# MotoControl_V1_0.net
KiCad netlist of a schematic drawn in Altium Designer
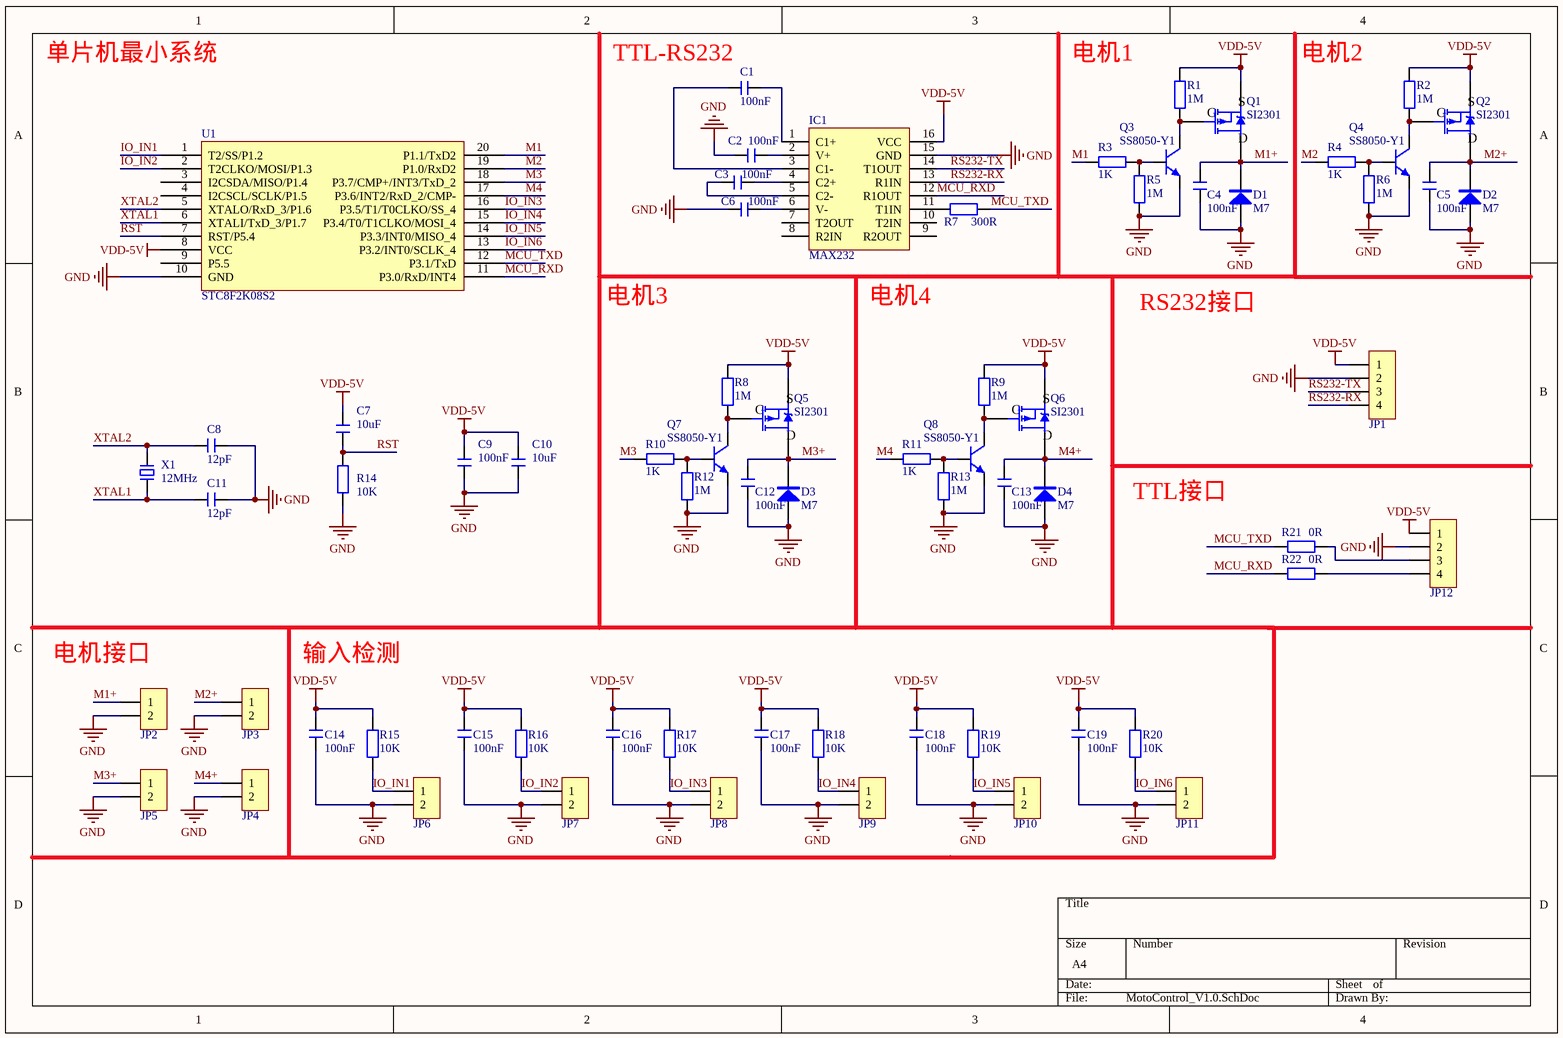
[diagram p0: MotoControl_V1.0.SchDoc]

(export (version "E")
  (design (tool "Eeschema 10.0.6"))
  (components
    (comp (ref "C1")
      (value "100nF")
      (footprint "C_0603")
      (description "无极性贴片电容")
      (fields (field (name "版权") "iSAIGU"))
      (libsource (lib "1-电阻-电容-电感") (part "C"))
    )
    (comp (ref "C2")
      (value "100nF")
      (footprint "C_0603")
      (description "无极性贴片电容")
      (fields (field (name "版权") "iSAIGU"))
      (libsource (lib "1-电阻-电容-电感") (part "C"))
    )
    (comp (ref "C3")
      (value "100nF")
      (footprint "C_0603")
      (description "无极性贴片电容")
      (fields (field (name "版权") "iSAIGU"))
      (libsource (lib "1-电阻-电容-电感") (part "C"))
    )
    (comp (ref "C4")
      (value "100nF")
      (footprint "C_0603")
      (description "无极性贴片电容")
      (fields (field (name "版权") "iSAIGU"))
      (libsource (lib "1-电阻-电容-电感") (part "C"))
    )
    (comp (ref "C5")
      (value "100nF")
      (footprint "C_0603")
      (description "无极性贴片电容")
      (fields (field (name "版权") "iSAIGU"))
      (libsource (lib "1-电阻-电容-电感") (part "C"))
    )
    (comp (ref "C6")
      (value "100nF")
      (footprint "C_0603")
      (description "无极性贴片电容")
      (fields (field (name "版权") "iSAIGU"))
      (libsource (lib "1-电阻-电容-电感") (part "C"))
    )
    (comp (ref "C7")
      (value "10uF")
      (footprint "C_0603")
      (description "无极性贴片电容")
      (fields (field (name "版权") "iSAIGU"))
      (libsource (lib "1-电阻-电容-电感") (part "C"))
    )
    (comp (ref "C8")
      (value "12pF")
      (footprint "C_0603")
      (description "无极性贴片电容")
      (fields (field (name "版权") "iSAIGU"))
      (libsource (lib "1-电阻-电容-电感") (part "C"))
    )
    (comp (ref "C9")
      (value "100nF")
      (footprint "C_0603")
      (description "无极性贴片电容")
      (fields (field (name "版权") "iSAIGU"))
      (libsource (lib "1-电阻-电容-电感") (part "C"))
    )
    (comp (ref "C10")
      (value "10uF")
      (footprint "C_0603")
      (description "无极性贴片电容")
      (fields (field (name "版权") "iSAIGU"))
      (libsource (lib "1-电阻-电容-电感") (part "C"))
    )
    (comp (ref "C11")
      (value "12pF")
      (footprint "C_0603")
      (description "无极性贴片电容")
      (fields (field (name "版权") "iSAIGU"))
      (libsource (lib "1-电阻-电容-电感") (part "C"))
    )
    (comp (ref "C12")
      (value "100nF")
      (footprint "C_0603")
      (description "无极性贴片电容")
      (fields (field (name "版权") "iSAIGU"))
      (libsource (lib "1-电阻-电容-电感") (part "C"))
    )
    (comp (ref "C13")
      (value "100nF")
      (footprint "C_0603")
      (description "无极性贴片电容")
      (fields (field (name "版权") "iSAIGU"))
      (libsource (lib "1-电阻-电容-电感") (part "C"))
    )
    (comp (ref "C14")
      (value "100nF")
      (footprint "C_0603")
      (description "无极性贴片电容")
      (fields (field (name "版权") "iSAIGU"))
      (libsource (lib "1-电阻-电容-电感") (part "C"))
    )
    (comp (ref "C15")
      (value "100nF")
      (footprint "C_0603")
      (description "无极性贴片电容")
      (fields (field (name "版权") "iSAIGU"))
      (libsource (lib "1-电阻-电容-电感") (part "C"))
    )
    (comp (ref "C16")
      (value "100nF")
      (footprint "C_0603")
      (description "无极性贴片电容")
      (fields (field (name "版权") "iSAIGU"))
      (libsource (lib "1-电阻-电容-电感") (part "C"))
    )
    (comp (ref "C17")
      (value "100nF")
      (footprint "C_0603")
      (description "无极性贴片电容")
      (fields (field (name "版权") "iSAIGU"))
      (libsource (lib "1-电阻-电容-电感") (part "C"))
    )
    (comp (ref "C18")
      (value "100nF")
      (footprint "C_0603")
      (description "无极性贴片电容")
      (fields (field (name "版权") "iSAIGU"))
      (libsource (lib "1-电阻-电容-电感") (part "C"))
    )
    (comp (ref "C19")
      (value "100nF")
      (footprint "C_0603")
      (description "无极性贴片电容")
      (fields (field (name "版权") "iSAIGU"))
      (libsource (lib "1-电阻-电容-电感") (part "C"))
    )
    (comp (ref "D1")
      (value "M7")
      (footprint "SMA")
      (description "整流二极管")
      (fields (field (name "版权") "iSAIGU"))
      (libsource (lib "2-二极管-整流桥") (part "M7"))
    )
    (comp (ref "D2")
      (value "M7")
      (footprint "SMA")
      (description "整流二极管")
      (fields (field (name "版权") "iSAIGU"))
      (libsource (lib "2-二极管-整流桥") (part "M7"))
    )
    (comp (ref "D3")
      (value "M7")
      (footprint "SMA")
      (description "整流二极管")
      (fields (field (name "版权") "iSAIGU"))
      (libsource (lib "2-二极管-整流桥") (part "M7"))
    )
    (comp (ref "D4")
      (value "M7")
      (footprint "SMA")
      (description "整流二极管")
      (fields (field (name "版权") "iSAIGU"))
      (libsource (lib "2-二极管-整流桥") (part "M7"))
    )
    (comp (ref "IC1")
      (value "MAX232")
      (footprint "SOP16_N")
      (fields (field (name "版权") "iSAIGU"))
      (libsource (lib "6-IC芯片") (part "MAX232"))
    )
    (comp (ref "JP1")
      (value "HDR-1X4")
      (footprint "XH2.54-4P")
      (description "4P接插件")
      (fields (field (name "版权") "iSAIGU"))
      (libsource (lib "4-接插件") (part "Header 4"))
    )
    (comp (ref "JP2")
      (value "HDR-1X2")
      (footprint "XH2.54-2P")
      (description "2P接插件")
      (fields (field (name "版权") "iSAIGU"))
      (libsource (lib "4-接插件") (part "Header 2"))
    )
    (comp (ref "JP3")
      (value "HDR-1X2")
      (footprint "XH2.54-2P")
      (description "2P接插件")
      (fields (field (name "版权") "iSAIGU"))
      (libsource (lib "4-接插件") (part "Header 2"))
    )
    (comp (ref "JP4")
      (value "HDR-1X2")
      (footprint "XH2.54-2P")
      (description "2P接插件")
      (fields (field (name "版权") "iSAIGU"))
      (libsource (lib "4-接插件") (part "Header 2"))
    )
    (comp (ref "JP5")
      (value "HDR-1X2")
      (footprint "XH2.54-2P")
      (description "2P接插件")
      (fields (field (name "版权") "iSAIGU"))
      (libsource (lib "4-接插件") (part "Header 2"))
    )
    (comp (ref "JP6")
      (value "HDR-1X2")
      (footprint "XH2.54-2P")
      (description "2P接插件")
      (fields (field (name "版权") "iSAIGU"))
      (libsource (lib "4-接插件") (part "Header 2"))
    )
    (comp (ref "JP7")
      (value "HDR-1X2")
      (footprint "XH2.54-2P")
      (description "2P接插件")
      (fields (field (name "版权") "iSAIGU"))
      (libsource (lib "4-接插件") (part "Header 2"))
    )
    (comp (ref "JP8")
      (value "HDR-1X2")
      (footprint "XH2.54-2P")
      (description "2P接插件")
      (fields (field (name "版权") "iSAIGU"))
      (libsource (lib "4-接插件") (part "Header 2"))
    )
    (comp (ref "JP9")
      (value "HDR-1X2")
      (footprint "XH2.54-2P")
      (description "2P接插件")
      (fields (field (name "版权") "iSAIGU"))
      (libsource (lib "4-接插件") (part "Header 2"))
    )
    (comp (ref "JP10")
      (value "HDR-1X2")
      (footprint "XH2.54-2P")
      (description "2P接插件")
      (fields (field (name "版权") "iSAIGU"))
      (libsource (lib "4-接插件") (part "Header 2"))
    )
    (comp (ref "JP11")
      (value "HDR-1X2")
      (footprint "XH2.54-2P")
      (description "2P接插件")
      (fields (field (name "版权") "iSAIGU"))
      (libsource (lib "4-接插件") (part "Header 2"))
    )
    (comp (ref "JP12")
      (value "HDR-1X4")
      (footprint "XH2.54-4P")
      (description "4P接插件")
      (fields (field (name "版权") "iSAIGU"))
      (libsource (lib "4-接插件") (part "Header 4"))
    )
    (comp (ref "Q1")
      (value "SI2301")
      (footprint "SOT23-3N")
      (description "P沟道场效应管")
      (fields (field (name "版权") "iSAIGU"))
      (libsource (lib "8-场效应管-可控硅") (part "SI2301"))
    )
    (comp (ref "Q2")
      (value "SI2301")
      (footprint "SOT23-3N")
      (description "P沟道场效应管")
      (fields (field (name "版权") "iSAIGU"))
      (libsource (lib "8-场效应管-可控硅") (part "SI2301"))
    )
    (comp (ref "Q3")
      (value "SS8050-Y1")
      (footprint "SOT23-3N")
      (description "高频放大-NPN型")
      (fields (field (name "版权") "iSAIGU"))
      (libsource (lib "3-三极管") (part "8050-Y1-SMD"))
    )
    (comp (ref "Q4")
      (value "SS8050-Y1")
      (footprint "SOT23-3N")
      (description "高频放大-NPN型")
      (fields (field (name "版权") "iSAIGU"))
      (libsource (lib "3-三极管") (part "8050-Y1-SMD"))
    )
    (comp (ref "Q5")
      (value "SI2301")
      (footprint "SOT23-3N")
      (description "P沟道场效应管")
      (fields (field (name "版权") "iSAIGU"))
      (libsource (lib "8-场效应管-可控硅") (part "SI2301"))
    )
    (comp (ref "Q6")
      (value "SI2301")
      (footprint "SOT23-3N")
      (description "P沟道场效应管")
      (fields (field (name "版权") "iSAIGU"))
      (libsource (lib "8-场效应管-可控硅") (part "SI2301"))
    )
    (comp (ref "Q7")
      (value "SS8050-Y1")
      (footprint "SOT23-3N")
      (description "高频放大-NPN型")
      (fields (field (name "版权") "iSAIGU"))
      (libsource (lib "3-三极管") (part "8050-Y1-SMD"))
    )
    (comp (ref "Q8")
      (value "SS8050-Y1")
      (footprint "SOT23-3N")
      (description "高频放大-NPN型")
      (fields (field (name "版权") "iSAIGU"))
      (libsource (lib "3-三极管") (part "8050-Y1-SMD"))
    )
    (comp (ref "R1")
      (value "1M")
      (footprint "R_0603")
      (description "±1%")
      (fields (field (name "版权") "iSAIGU"))
      (libsource (lib "1-电阻-电容-电感") (part "R"))
    )
    (comp (ref "R2")
      (value "1M")
      (footprint "R_0603")
      (description "±1%")
      (fields (field (name "版权") "iSAIGU"))
      (libsource (lib "1-电阻-电容-电感") (part "R"))
    )
    (comp (ref "R3")
      (value "1K")
      (footprint "R_0603")
      (description "±1%")
      (fields (field (name "版权") "iSAIGU"))
      (libsource (lib "1-电阻-电容-电感") (part "R"))
    )
    (comp (ref "R4")
      (value "1K")
      (footprint "R_0603")
      (description "±1%")
      (fields (field (name "版权") "iSAIGU"))
      (libsource (lib "1-电阻-电容-电感") (part "R"))
    )
    (comp (ref "R5")
      (value "1M")
      (footprint "R_0603")
      (description "±1%")
      (fields (field (name "版权") "iSAIGU"))
      (libsource (lib "1-电阻-电容-电感") (part "R"))
    )
    (comp (ref "R6")
      (value "1M")
      (footprint "R_0603")
      (description "±1%")
      (fields (field (name "版权") "iSAIGU"))
      (libsource (lib "1-电阻-电容-电感") (part "R"))
    )
    (comp (ref "R7")
      (value "300R")
      (footprint "R_0603")
      (description "±1%")
      (fields (field (name "版权") "iSAIGU"))
      (libsource (lib "1-电阻-电容-电感") (part "R"))
    )
    (comp (ref "R8")
      (value "1M")
      (footprint "R_0603")
      (description "±1%")
      (fields (field (name "版权") "iSAIGU"))
      (libsource (lib "1-电阻-电容-电感") (part "R"))
    )
    (comp (ref "R9")
      (value "1M")
      (footprint "R_0603")
      (description "±1%")
      (fields (field (name "版权") "iSAIGU"))
      (libsource (lib "1-电阻-电容-电感") (part "R"))
    )
    (comp (ref "R10")
      (value "1K")
      (footprint "R_0603")
      (description "±1%")
      (fields (field (name "版权") "iSAIGU"))
      (libsource (lib "1-电阻-电容-电感") (part "R"))
    )
    (comp (ref "R11")
      (value "1K")
      (footprint "R_0603")
      (description "±1%")
      (fields (field (name "版权") "iSAIGU"))
      (libsource (lib "1-电阻-电容-电感") (part "R"))
    )
    (comp (ref "R12")
      (value "1M")
      (footprint "R_0603")
      (description "±1%")
      (fields (field (name "版权") "iSAIGU"))
      (libsource (lib "1-电阻-电容-电感") (part "R"))
    )
    (comp (ref "R13")
      (value "1M")
      (footprint "R_0603")
      (description "±1%")
      (fields (field (name "版权") "iSAIGU"))
      (libsource (lib "1-电阻-电容-电感") (part "R"))
    )
    (comp (ref "R14")
      (value "10K")
      (footprint "R_0603")
      (description "贴片电阻")
      (fields (field (name "版权") "iSAIGU"))
      (libsource (lib "1-电阻-电容-电感") (part "R"))
    )
    (comp (ref "R15")
      (value "10K")
      (footprint "R_0603")
      (description "贴片电阻")
      (fields (field (name "版权") "iSAIGU"))
      (libsource (lib "1-电阻-电容-电感") (part "R"))
    )
    (comp (ref "R16")
      (value "10K")
      (footprint "R_0603")
      (description "贴片电阻")
      (fields (field (name "版权") "iSAIGU"))
      (libsource (lib "1-电阻-电容-电感") (part "R"))
    )
    (comp (ref "R17")
      (value "10K")
      (footprint "R_0603")
      (description "贴片电阻")
      (fields (field (name "版权") "iSAIGU"))
      (libsource (lib "1-电阻-电容-电感") (part "R"))
    )
    (comp (ref "R18")
      (value "10K")
      (footprint "R_0603")
      (description "贴片电阻")
      (fields (field (name "版权") "iSAIGU"))
      (libsource (lib "1-电阻-电容-电感") (part "R"))
    )
    (comp (ref "R19")
      (value "10K")
      (footprint "R_0603")
      (description "贴片电阻")
      (fields (field (name "版权") "iSAIGU"))
      (libsource (lib "1-电阻-电容-电感") (part "R"))
    )
    (comp (ref "R20")
      (value "10K")
      (footprint "R_0603")
      (description "贴片电阻")
      (fields (field (name "版权") "iSAIGU"))
      (libsource (lib "1-电阻-电容-电感") (part "R"))
    )
    (comp (ref "R21")
      (value "0R")
      (footprint "R_0603")
      (description "贴片电阻")
      (fields (field (name "版权") "iSAIGU"))
      (libsource (lib "1-电阻-电容-电感") (part "R"))
    )
    (comp (ref "R22")
      (value "0R")
      (footprint "R_0603")
      (description "贴片电阻")
      (fields (field (name "版权") "iSAIGU"))
      (libsource (lib "1-电阻-电容-电感") (part "R"))
    )
    (comp (ref "U1")
      (value "STC8F2K08S2")
      (footprint "TSSOP20_N")
      (description "STC单片机")
      (libsource (lib "STC系列单片机") (part "STC8F2K08S2"))
    )
    (comp (ref "X1")
      (value "12MHz")
      (footprint "SMD-3215_2P")
      (description "2脚晶振")
      (fields (field (name "版权") "iSAIGU"))
      (libsource (lib "9-保险丝-晶振") (part "XTAL-2"))
    )
  )
  (nets
    (net (code "1") (name "/IO_IN1") (class "Default")
      (node (ref "JP6") (pin "1") (pinfunction "1_1") (pintype "passive"))
      (node (ref "R15") (pin "1") (pinfunction "1_1") (pintype "passive"))
      (node (ref "U1") (pin "1") (pinfunction "T2/SS/P1.2_1") (pintype "passive"))
    )
    (net (code "2") (name "/IO_IN2") (class "Default")
      (node (ref "JP7") (pin "1") (pinfunction "1_1") (pintype "passive"))
      (node (ref "R16") (pin "1") (pinfunction "1_1") (pintype "passive"))
      (node (ref "U1") (pin "2") (pinfunction "T2CLKO/MOSI/P1.3_2") (pintype "passive"))
    )
    (net (code "3") (name "/IO_IN3") (class "Default")
      (node (ref "JP8") (pin "1") (pinfunction "1_1") (pintype "passive"))
      (node (ref "R17") (pin "1") (pinfunction "1_1") (pintype "passive"))
      (node (ref "U1") (pin "16") (pinfunction "P3.5/T1/T0CLKO/SS_4_16") (pintype "passive"))
    )
    (net (code "4") (name "/IO_IN4") (class "Default")
      (node (ref "JP9") (pin "1") (pinfunction "1_1") (pintype "passive"))
      (node (ref "R18") (pin "1") (pinfunction "1_1") (pintype "passive"))
      (node (ref "U1") (pin "15") (pinfunction "P3.4/T0/T1CLKO/MOSI_4_15") (pintype "passive"))
    )
    (net (code "5") (name "/IO_IN5") (class "Default")
      (node (ref "JP10") (pin "1") (pinfunction "1_1") (pintype "passive"))
      (node (ref "R19") (pin "1") (pinfunction "1_1") (pintype "passive"))
      (node (ref "U1") (pin "14") (pinfunction "P3.3/INT0/MISO_4_14") (pintype "passive"))
    )
    (net (code "6") (name "/IO_IN6") (class "Default")
      (node (ref "JP11") (pin "1") (pinfunction "1_1") (pintype "passive"))
      (node (ref "R20") (pin "1") (pinfunction "1_1") (pintype "passive"))
      (node (ref "U1") (pin "13") (pinfunction "P3.2/INT0/SCLK_4_13") (pintype "passive"))
    )
    (net (code "7") (name "/M1") (class "Default")
      (node (ref "R3") (pin "1") (pinfunction "1_1") (pintype "passive"))
      (node (ref "U1") (pin "20") (pinfunction "P1.1/TxD2_20") (pintype "passive"))
    )
    (net (code "8") (name "/M1+") (class "Default")
      (node (ref "C4") (pin "1") (pinfunction "1_1") (pintype "passive"))
      (node (ref "D1") (pin "2") (pinfunction "K_2") (pintype "passive"))
      (node (ref "JP2") (pin "1") (pinfunction "1_1") (pintype "passive"))
      (node (ref "Q1") (pin "3") (pinfunction "D_3") (pintype "passive"))
    )
    (net (code "9") (name "/M2") (class "Default")
      (node (ref "R4") (pin "1") (pinfunction "1_1") (pintype "passive"))
      (node (ref "U1") (pin "19") (pinfunction "P1.0/RxD2_19") (pintype "passive"))
    )
    (net (code "10") (name "/M2+") (class "Default")
      (node (ref "C5") (pin "1") (pinfunction "1_1") (pintype "passive"))
      (node (ref "D2") (pin "2") (pinfunction "K_2") (pintype "passive"))
      (node (ref "JP3") (pin "1") (pinfunction "1_1") (pintype "passive"))
      (node (ref "Q2") (pin "3") (pinfunction "D_3") (pintype "passive"))
    )
    (net (code "11") (name "/M3") (class "Default")
      (node (ref "R10") (pin "1") (pinfunction "1_1") (pintype "passive"))
      (node (ref "U1") (pin "18") (pinfunction "P3.7/CMP+/INT3/TxD_2_18") (pintype "passive"))
    )
    (net (code "12") (name "/M3+") (class "Default")
      (node (ref "C12") (pin "1") (pinfunction "1_1") (pintype "passive"))
      (node (ref "D3") (pin "2") (pinfunction "K_2") (pintype "passive"))
      (node (ref "JP5") (pin "1") (pinfunction "1_1") (pintype "passive"))
      (node (ref "Q5") (pin "3") (pinfunction "D_3") (pintype "passive"))
    )
    (net (code "13") (name "/M4") (class "Default")
      (node (ref "R11") (pin "1") (pinfunction "1_1") (pintype "passive"))
      (node (ref "U1") (pin "17") (pinfunction "P3.6/INT2/RxD_2/CMP-_17") (pintype "passive"))
    )
    (net (code "14") (name "/M4+") (class "Default")
      (node (ref "C13") (pin "1") (pinfunction "1_1") (pintype "passive"))
      (node (ref "D4") (pin "2") (pinfunction "K_2") (pintype "passive"))
      (node (ref "JP4") (pin "1") (pinfunction "1_1") (pintype "passive"))
      (node (ref "Q6") (pin "3") (pinfunction "D_3") (pintype "passive"))
    )
    (net (code "15") (name "/MCU_RXD") (class "Default")
      (node (ref "IC1") (pin "12") (pinfunction "R1OUT_12") (pintype "passive"))
      (node (ref "R22") (pin "1") (pinfunction "1_1") (pintype "passive"))
      (node (ref "U1") (pin "11") (pinfunction "P3.0/RxD/INT4_11") (pintype "passive"))
    )
    (net (code "16") (name "/MCU_TXD") (class "Default")
      (node (ref "R21") (pin "1") (pinfunction "1_1") (pintype "passive"))
      (node (ref "R7") (pin "2") (pinfunction "2_2") (pintype "passive"))
      (node (ref "U1") (pin "12") (pinfunction "P3.1/TxD_12") (pintype "passive"))
    )
    (net (code "17") (name "/RS232-RX") (class "Default")
      (node (ref "IC1") (pin "13") (pinfunction "R1IN_13") (pintype "passive"))
      (node (ref "JP1") (pin "4") (pinfunction "4_4") (pintype "passive"))
    )
    (net (code "18") (name "/RS232-TX") (class "Default")
      (node (ref "IC1") (pin "14") (pinfunction "T1OUT_14") (pintype "passive"))
      (node (ref "JP1") (pin "3") (pinfunction "3_3") (pintype "passive"))
    )
    (net (code "19") (name "/RST") (class "Default")
      (node (ref "C7") (pin "1") (pinfunction "1_1") (pintype "passive"))
      (node (ref "R14") (pin "2") (pinfunction "2_2") (pintype "passive"))
      (node (ref "U1") (pin "7") (pinfunction "RST/P5.4_7") (pintype "passive"))
    )
    (net (code "20") (name "/XTAL1") (class "Default")
      (node (ref "C11") (pin "1") (pinfunction "1_1") (pintype "passive"))
      (node (ref "U1") (pin "6") (pinfunction "XTALI/TxD_3/P1.7_6") (pintype "passive"))
      (node (ref "X1") (pin "1") (pinfunction "1_1") (pintype "passive"))
    )
    (net (code "21") (name "/XTAL2") (class "Default")
      (node (ref "C8") (pin "1") (pinfunction "1_1") (pintype "passive"))
      (node (ref "U1") (pin "5") (pinfunction "XTALO/RxD_3/P1.6_5") (pintype "passive"))
      (node (ref "X1") (pin "2") (pinfunction "2_2") (pintype "passive"))
    )
    (net (code "22") (name "GND") (class "Default")
      (node (ref "C10") (pin "1") (pinfunction "1_1") (pintype "passive"))
      (node (ref "C11") (pin "2") (pinfunction "2_2") (pintype "passive"))
      (node (ref "C12") (pin "2") (pinfunction "2_2") (pintype "passive"))
      (node (ref "C13") (pin "2") (pinfunction "2_2") (pintype "passive"))
      (node (ref "C14") (pin "1") (pinfunction "1_1") (pintype "passive"))
      (node (ref "C15") (pin "1") (pinfunction "1_1") (pintype "passive"))
      (node (ref "C16") (pin "1") (pinfunction "1_1") (pintype "passive"))
      (node (ref "C17") (pin "1") (pinfunction "1_1") (pintype "passive"))
      (node (ref "C18") (pin "1") (pinfunction "1_1") (pintype "passive"))
      (node (ref "C19") (pin "1") (pinfunction "1_1") (pintype "passive"))
      (node (ref "C2") (pin "1") (pinfunction "1_1") (pintype "passive"))
      (node (ref "C4") (pin "2") (pinfunction "2_2") (pintype "passive"))
      (node (ref "C5") (pin "2") (pinfunction "2_2") (pintype "passive"))
      (node (ref "C6") (pin "1") (pinfunction "1_1") (pintype "passive"))
      (node (ref "C8") (pin "2") (pinfunction "2_2") (pintype "passive"))
      (node (ref "C9") (pin "1") (pinfunction "1_1") (pintype "passive"))
      (node (ref "D1") (pin "1") (pinfunction "A_1") (pintype "passive"))
      (node (ref "D2") (pin "1") (pinfunction "A_1") (pintype "passive"))
      (node (ref "D3") (pin "1") (pinfunction "A_1") (pintype "passive"))
      (node (ref "D4") (pin "1") (pinfunction "A_1") (pintype "passive"))
      (node (ref "IC1") (pin "15") (pinfunction "GND_15") (pintype "passive"))
      (node (ref "JP1") (pin "2") (pinfunction "2_2") (pintype "passive"))
      (node (ref "JP10") (pin "2") (pinfunction "2_2") (pintype "passive"))
      (node (ref "JP11") (pin "2") (pinfunction "2_2") (pintype "passive"))
      (node (ref "JP12") (pin "2") (pinfunction "2_2") (pintype "passive"))
      (node (ref "JP2") (pin "2") (pinfunction "2_2") (pintype "passive"))
      (node (ref "JP3") (pin "2") (pinfunction "2_2") (pintype "passive"))
      (node (ref "JP4") (pin "2") (pinfunction "2_2") (pintype "passive"))
      (node (ref "JP5") (pin "2") (pinfunction "2_2") (pintype "passive"))
      (node (ref "JP6") (pin "2") (pinfunction "2_2") (pintype "passive"))
      (node (ref "JP7") (pin "2") (pinfunction "2_2") (pintype "passive"))
      (node (ref "JP8") (pin "2") (pinfunction "2_2") (pintype "passive"))
      (node (ref "JP9") (pin "2") (pinfunction "2_2") (pintype "passive"))
      (node (ref "Q3") (pin "2") (pinfunction "E_2") (pintype "passive"))
      (node (ref "Q4") (pin "2") (pinfunction "E_2") (pintype "passive"))
      (node (ref "Q7") (pin "2") (pinfunction "E_2") (pintype "passive"))
      (node (ref "Q8") (pin "2") (pinfunction "E_2") (pintype "passive"))
      (node (ref "R12") (pin "1") (pinfunction "1_1") (pintype "passive"))
      (node (ref "R13") (pin "1") (pinfunction "1_1") (pintype "passive"))
      (node (ref "R14") (pin "1") (pinfunction "1_1") (pintype "passive"))
      (node (ref "R5") (pin "1") (pinfunction "1_1") (pintype "passive"))
      (node (ref "R6") (pin "1") (pinfunction "1_1") (pintype "passive"))
      (node (ref "U1") (pin "10") (pinfunction "GND_10") (pintype "passive"))
    )
    (net (code "23") (name "Net-(IC1-C1+)") (class "Default")
      (node (ref "C1") (pin "2") (pinfunction "2_2") (pintype "passive"))
      (node (ref "IC1") (pin "1") (pinfunction "C1+_1") (pintype "passive"))
    )
    (net (code "24") (name "Net-(IC1-C1-)") (class "Default")
      (node (ref "C1") (pin "1") (pinfunction "1_1") (pintype "passive"))
      (node (ref "IC1") (pin "3") (pinfunction "C1-_3") (pintype "passive"))
    )
    (net (code "25") (name "Net-(IC1-C2+)") (class "Default")
      (node (ref "C3") (pin "2") (pinfunction "2_2") (pintype "passive"))
      (node (ref "IC1") (pin "4") (pinfunction "C2+_4") (pintype "passive"))
    )
    (net (code "26") (name "Net-(IC1-C2-)") (class "Default")
      (node (ref "C3") (pin "1") (pinfunction "1_1") (pintype "passive"))
      (node (ref "IC1") (pin "5") (pinfunction "C2-_5") (pintype "passive"))
    )
    (net (code "27") (name "Net-(IC1-T1IN)") (class "Default")
      (node (ref "IC1") (pin "11") (pinfunction "T1IN_11") (pintype "passive"))
      (node (ref "R7") (pin "1") (pinfunction "1_1") (pintype "passive"))
    )
    (net (code "28") (name "Net-(IC1-V+)") (class "Default")
      (node (ref "C2") (pin "2") (pinfunction "2_2") (pintype "passive"))
      (node (ref "IC1") (pin "2") (pinfunction "V+_2") (pintype "passive"))
    )
    (net (code "29") (name "Net-(IC1-V-)") (class "Default")
      (node (ref "C6") (pin "2") (pinfunction "2_2") (pintype "passive"))
      (node (ref "IC1") (pin "6") (pinfunction "V-_6") (pintype "passive"))
    )
    (net (code "30") (name "Net-(JP12-Pad3)") (class "Default")
      (node (ref "JP12") (pin "3") (pinfunction "3_3") (pintype "passive"))
      (node (ref "R21") (pin "2") (pinfunction "2_2") (pintype "passive"))
    )
    (net (code "31") (name "Net-(JP12-Pad4)") (class "Default")
      (node (ref "JP12") (pin "4") (pinfunction "4_4") (pintype "passive"))
      (node (ref "R22") (pin "2") (pinfunction "2_2") (pintype "passive"))
    )
    (net (code "32") (name "Net-(Q1-G)") (class "Default")
      (node (ref "Q1") (pin "1") (pinfunction "G_1") (pintype "passive"))
      (node (ref "Q3") (pin "3") (pinfunction "C_3") (pintype "passive"))
      (node (ref "R1") (pin "2") (pinfunction "2_2") (pintype "passive"))
    )
    (net (code "33") (name "Net-(Q2-G)") (class "Default")
      (node (ref "Q2") (pin "1") (pinfunction "G_1") (pintype "passive"))
      (node (ref "Q4") (pin "3") (pinfunction "C_3") (pintype "passive"))
      (node (ref "R2") (pin "2") (pinfunction "2_2") (pintype "passive"))
    )
    (net (code "34") (name "Net-(Q3-B)") (class "Default")
      (node (ref "Q3") (pin "1") (pinfunction "B_1") (pintype "passive"))
      (node (ref "R3") (pin "2") (pinfunction "2_2") (pintype "passive"))
      (node (ref "R5") (pin "2") (pinfunction "2_2") (pintype "passive"))
    )
    (net (code "35") (name "Net-(Q4-B)") (class "Default")
      (node (ref "Q4") (pin "1") (pinfunction "B_1") (pintype "passive"))
      (node (ref "R4") (pin "2") (pinfunction "2_2") (pintype "passive"))
      (node (ref "R6") (pin "2") (pinfunction "2_2") (pintype "passive"))
    )
    (net (code "36") (name "Net-(Q5-G)") (class "Default")
      (node (ref "Q5") (pin "1") (pinfunction "G_1") (pintype "passive"))
      (node (ref "Q7") (pin "3") (pinfunction "C_3") (pintype "passive"))
      (node (ref "R8") (pin "2") (pinfunction "2_2") (pintype "passive"))
    )
    (net (code "37") (name "Net-(Q6-G)") (class "Default")
      (node (ref "Q6") (pin "1") (pinfunction "G_1") (pintype "passive"))
      (node (ref "Q8") (pin "3") (pinfunction "C_3") (pintype "passive"))
      (node (ref "R9") (pin "2") (pinfunction "2_2") (pintype "passive"))
    )
    (net (code "38") (name "Net-(Q7-B)") (class "Default")
      (node (ref "Q7") (pin "1") (pinfunction "B_1") (pintype "passive"))
      (node (ref "R10") (pin "2") (pinfunction "2_2") (pintype "passive"))
      (node (ref "R12") (pin "2") (pinfunction "2_2") (pintype "passive"))
    )
    (net (code "39") (name "Net-(Q8-B)") (class "Default")
      (node (ref "Q8") (pin "1") (pinfunction "B_1") (pintype "passive"))
      (node (ref "R11") (pin "2") (pinfunction "2_2") (pintype "passive"))
      (node (ref "R13") (pin "2") (pinfunction "2_2") (pintype "passive"))
    )
    (net (code "40") (name "VDD-5V") (class "Default")
      (node (ref "C10") (pin "2") (pinfunction "2_2") (pintype "passive"))
      (node (ref "C14") (pin "2") (pinfunction "2_2") (pintype "passive"))
      (node (ref "C15") (pin "2") (pinfunction "2_2") (pintype "passive"))
      (node (ref "C16") (pin "2") (pinfunction "2_2") (pintype "passive"))
      (node (ref "C17") (pin "2") (pinfunction "2_2") (pintype "passive"))
      (node (ref "C18") (pin "2") (pinfunction "2_2") (pintype "passive"))
      (node (ref "C19") (pin "2") (pinfunction "2_2") (pintype "passive"))
      (node (ref "C7") (pin "2") (pinfunction "2_2") (pintype "passive"))
      (node (ref "C9") (pin "2") (pinfunction "2_2") (pintype "passive"))
      (node (ref "IC1") (pin "16") (pinfunction "VCC_16") (pintype "passive"))
      (node (ref "JP1") (pin "1") (pinfunction "1_1") (pintype "passive"))
      (node (ref "JP12") (pin "1") (pinfunction "1_1") (pintype "passive"))
      (node (ref "Q1") (pin "2") (pinfunction "S_2") (pintype "passive"))
      (node (ref "Q2") (pin "2") (pinfunction "S_2") (pintype "passive"))
      (node (ref "Q5") (pin "2") (pinfunction "S_2") (pintype "passive"))
      (node (ref "Q6") (pin "2") (pinfunction "S_2") (pintype "passive"))
      (node (ref "R1") (pin "1") (pinfunction "1_1") (pintype "passive"))
      (node (ref "R15") (pin "2") (pinfunction "2_2") (pintype "passive"))
      (node (ref "R16") (pin "2") (pinfunction "2_2") (pintype "passive"))
      (node (ref "R17") (pin "2") (pinfunction "2_2") (pintype "passive"))
      (node (ref "R18") (pin "2") (pinfunction "2_2") (pintype "passive"))
      (node (ref "R19") (pin "2") (pinfunction "2_2") (pintype "passive"))
      (node (ref "R2") (pin "1") (pinfunction "1_1") (pintype "passive"))
      (node (ref "R20") (pin "2") (pinfunction "2_2") (pintype "passive"))
      (node (ref "R8") (pin "1") (pinfunction "1_1") (pintype "passive"))
      (node (ref "R9") (pin "1") (pinfunction "1_1") (pintype "passive"))
      (node (ref "U1") (pin "8") (pinfunction "VCC_8") (pintype "passive"))
    )
    (net (code "41") (name "unconnected-(IC1-R2IN-Pad8)") (class "Default")
      (node (ref "IC1") (pin "8") (pinfunction "R2IN_8") (pintype "passive"))
    )
    (net (code "42") (name "unconnected-(IC1-R2OUT-Pad9)") (class "Default")
      (node (ref "IC1") (pin "9") (pinfunction "R2OUT_9") (pintype "passive"))
    )
    (net (code "43") (name "unconnected-(IC1-T2IN-Pad10)") (class "Default")
      (node (ref "IC1") (pin "10") (pinfunction "T2IN_10") (pintype "passive"))
    )
    (net (code "44") (name "unconnected-(IC1-T2OUT-Pad7)") (class "Default")
      (node (ref "IC1") (pin "7") (pinfunction "T2OUT_7") (pintype "passive"))
    )
    (net (code "45") (name "unconnected-(U1-I2CSCL{slash}SCLK{slash}P1.5-Pad4)") (class "Default")
      (node (ref "U1") (pin "4") (pinfunction "I2CSCL/SCLK/P1.5_4") (pintype "passive"))
    )
    (net (code "46") (name "unconnected-(U1-I2CSDA{slash}MISO{slash}P1.4-Pad3)") (class "Default")
      (node (ref "U1") (pin "3") (pinfunction "I2CSDA/MISO/P1.4_3") (pintype "passive"))
    )
    (net (code "47") (name "unconnected-(U1-P5.5-Pad9)") (class "Default")
      (node (ref "U1") (pin "9") (pinfunction "P5.5_9") (pintype "passive"))
    )
  )
)
